# MiniPowerAdaptorInline.net
KiCad netlist of a schematic drawn in EAGLE
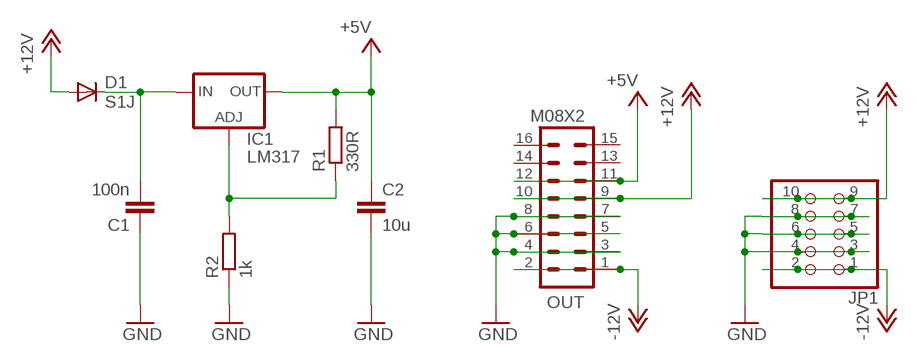
[diagram p0: schematic, sheet 1]

(export (version "E")
  (design (tool "Eeschema 10.0.6"))
  (components
    (comp (ref "C1")
      (value "100n")
      (footprint "eagle-import:C0603")
      (libsource (lib "eagle-import") (part "C-EUC0603"))
    )
    (comp (ref "C2")
      (value "10u")
      (footprint "eagle-import:C1206")
      (libsource (lib "eagle-import") (part "C-EUC1206"))
    )
    (comp (ref "D1")
      (value "S1J")
      (footprint "eagle-import:SMA-DIODE")
      (libsource (lib "eagle-import") (part "DIODESMA"))
    )
    (comp (ref "IC1")
      (value "LM317")
      (footprint "eagle-import:DPACK")
      (libsource (lib "eagle-import") (part "LM317?MDT"))
    )
    (comp (ref "JP1")
      (value "PINHD-2X5")
      (footprint "eagle-import:2X05")
      (libsource (lib "eagle-import") (part "PINHD-2X5"))
    )
    (comp (ref "OUT")
      (value "M08X2")
      (footprint "eagle-import:2X8")
      (libsource (lib "eagle-import") (part "M08X2"))
    )
    (comp (ref "R1")
      (value "330R")
      (footprint "eagle-import:0603")
      (libsource (lib "eagle-import") (part "R-EU_0603"))
    )
    (comp (ref "R2")
      (value "1k")
      (footprint "eagle-import:0603")
      (libsource (lib "eagle-import") (part "R-EU_0603"))
    )
  )
  (nets
    (net (code "1") (name "+5V") (class "Default")
      (node (ref "C2") (pin "1") (pinfunction "1_1") (pintype "passive"))
      (node (ref "IC1") (pin "4") (pinfunction "OUT_4") (pintype "passive"))
      (node (ref "OUT") (pin "11") (pinfunction "11_11") (pintype "passive"))
      (node (ref "OUT") (pin "12") (pinfunction "12_12") (pintype "passive"))
      (node (ref "R1") (pin "2") (pinfunction "2_2") (pintype "passive"))
    )
    (net (code "2") (name "+12V") (class "Default")
      (node (ref "D1") (pin "A") (pinfunction "A_A") (pintype "passive"))
      (node (ref "JP1") (pin "10") (pinfunction "10_10") (pintype "passive"))
      (node (ref "JP1") (pin "9") (pinfunction "9_9") (pintype "passive"))
      (node (ref "OUT") (pin "10") (pinfunction "10_10") (pintype "passive"))
      (node (ref "OUT") (pin "9") (pinfunction "9_9") (pintype "passive"))
    )
    (net (code "3") (name "-12V") (class "Default")
      (node (ref "JP1") (pin "1") (pinfunction "1_1") (pintype "passive"))
      (node (ref "JP1") (pin "2") (pinfunction "2_2") (pintype "passive"))
      (node (ref "OUT") (pin "1") (pinfunction "1_1") (pintype "passive"))
      (node (ref "OUT") (pin "2") (pinfunction "2_2") (pintype "passive"))
    )
    (net (code "4") (name "GND") (class "Default")
      (node (ref "C1") (pin "1") (pinfunction "1_1") (pintype "passive"))
      (node (ref "C2") (pin "2") (pinfunction "2_2") (pintype "passive"))
      (node (ref "JP1") (pin "3") (pinfunction "3_3") (pintype "passive"))
      (node (ref "JP1") (pin "4") (pinfunction "4_4") (pintype "passive"))
      (node (ref "JP1") (pin "5") (pinfunction "5_5") (pintype "passive"))
      (node (ref "JP1") (pin "6") (pinfunction "6_6") (pintype "passive"))
      (node (ref "JP1") (pin "7") (pinfunction "7_7") (pintype "passive"))
      (node (ref "JP1") (pin "8") (pinfunction "8_8") (pintype "passive"))
      (node (ref "OUT") (pin "3") (pinfunction "3_3") (pintype "passive"))
      (node (ref "OUT") (pin "4") (pinfunction "4_4") (pintype "passive"))
      (node (ref "OUT") (pin "5") (pinfunction "5_5") (pintype "passive"))
      (node (ref "OUT") (pin "6") (pinfunction "6_6") (pintype "passive"))
      (node (ref "OUT") (pin "7") (pinfunction "7_7") (pintype "passive"))
      (node (ref "OUT") (pin "8") (pinfunction "8_8") (pintype "passive"))
      (node (ref "R2") (pin "1") (pinfunction "1_1") (pintype "passive"))
    )
    (net (code "5") (name "Net-(IC1-ADJ)") (class "Default")
      (node (ref "IC1") (pin "1") (pinfunction "ADJ_1") (pintype "input"))
      (node (ref "R1") (pin "1") (pinfunction "1_1") (pintype "passive"))
      (node (ref "R2") (pin "2") (pinfunction "2_2") (pintype "passive"))
    )
    (net (code "6") (name "Net-(IC1-IN)") (class "Default")
      (node (ref "C1") (pin "2") (pinfunction "2_2") (pintype "passive"))
      (node (ref "D1") (pin "C") (pinfunction "C_C") (pintype "passive"))
      (node (ref "IC1") (pin "3") (pinfunction "IN_3") (pintype "input"))
    )
    (net (code "7") (name "unconnected-(OUT-Pad13)") (class "Default")
      (node (ref "OUT") (pin "13") (pinfunction "13_13") (pintype "passive"))
    )
    (net (code "8") (name "unconnected-(OUT-Pad14)") (class "Default")
      (node (ref "OUT") (pin "14") (pinfunction "14_14") (pintype "passive"))
    )
    (net (code "9") (name "unconnected-(OUT-Pad15)") (class "Default")
      (node (ref "OUT") (pin "15") (pinfunction "15_15") (pintype "passive"))
    )
    (net (code "10") (name "unconnected-(OUT-Pad16)") (class "Default")
      (node (ref "OUT") (pin "16") (pinfunction "16_16") (pintype "passive"))
    )
  )
)
